# Low_jitter_CLK_bypass.net
KiCad netlist of a schematic drawn in Altium Designer
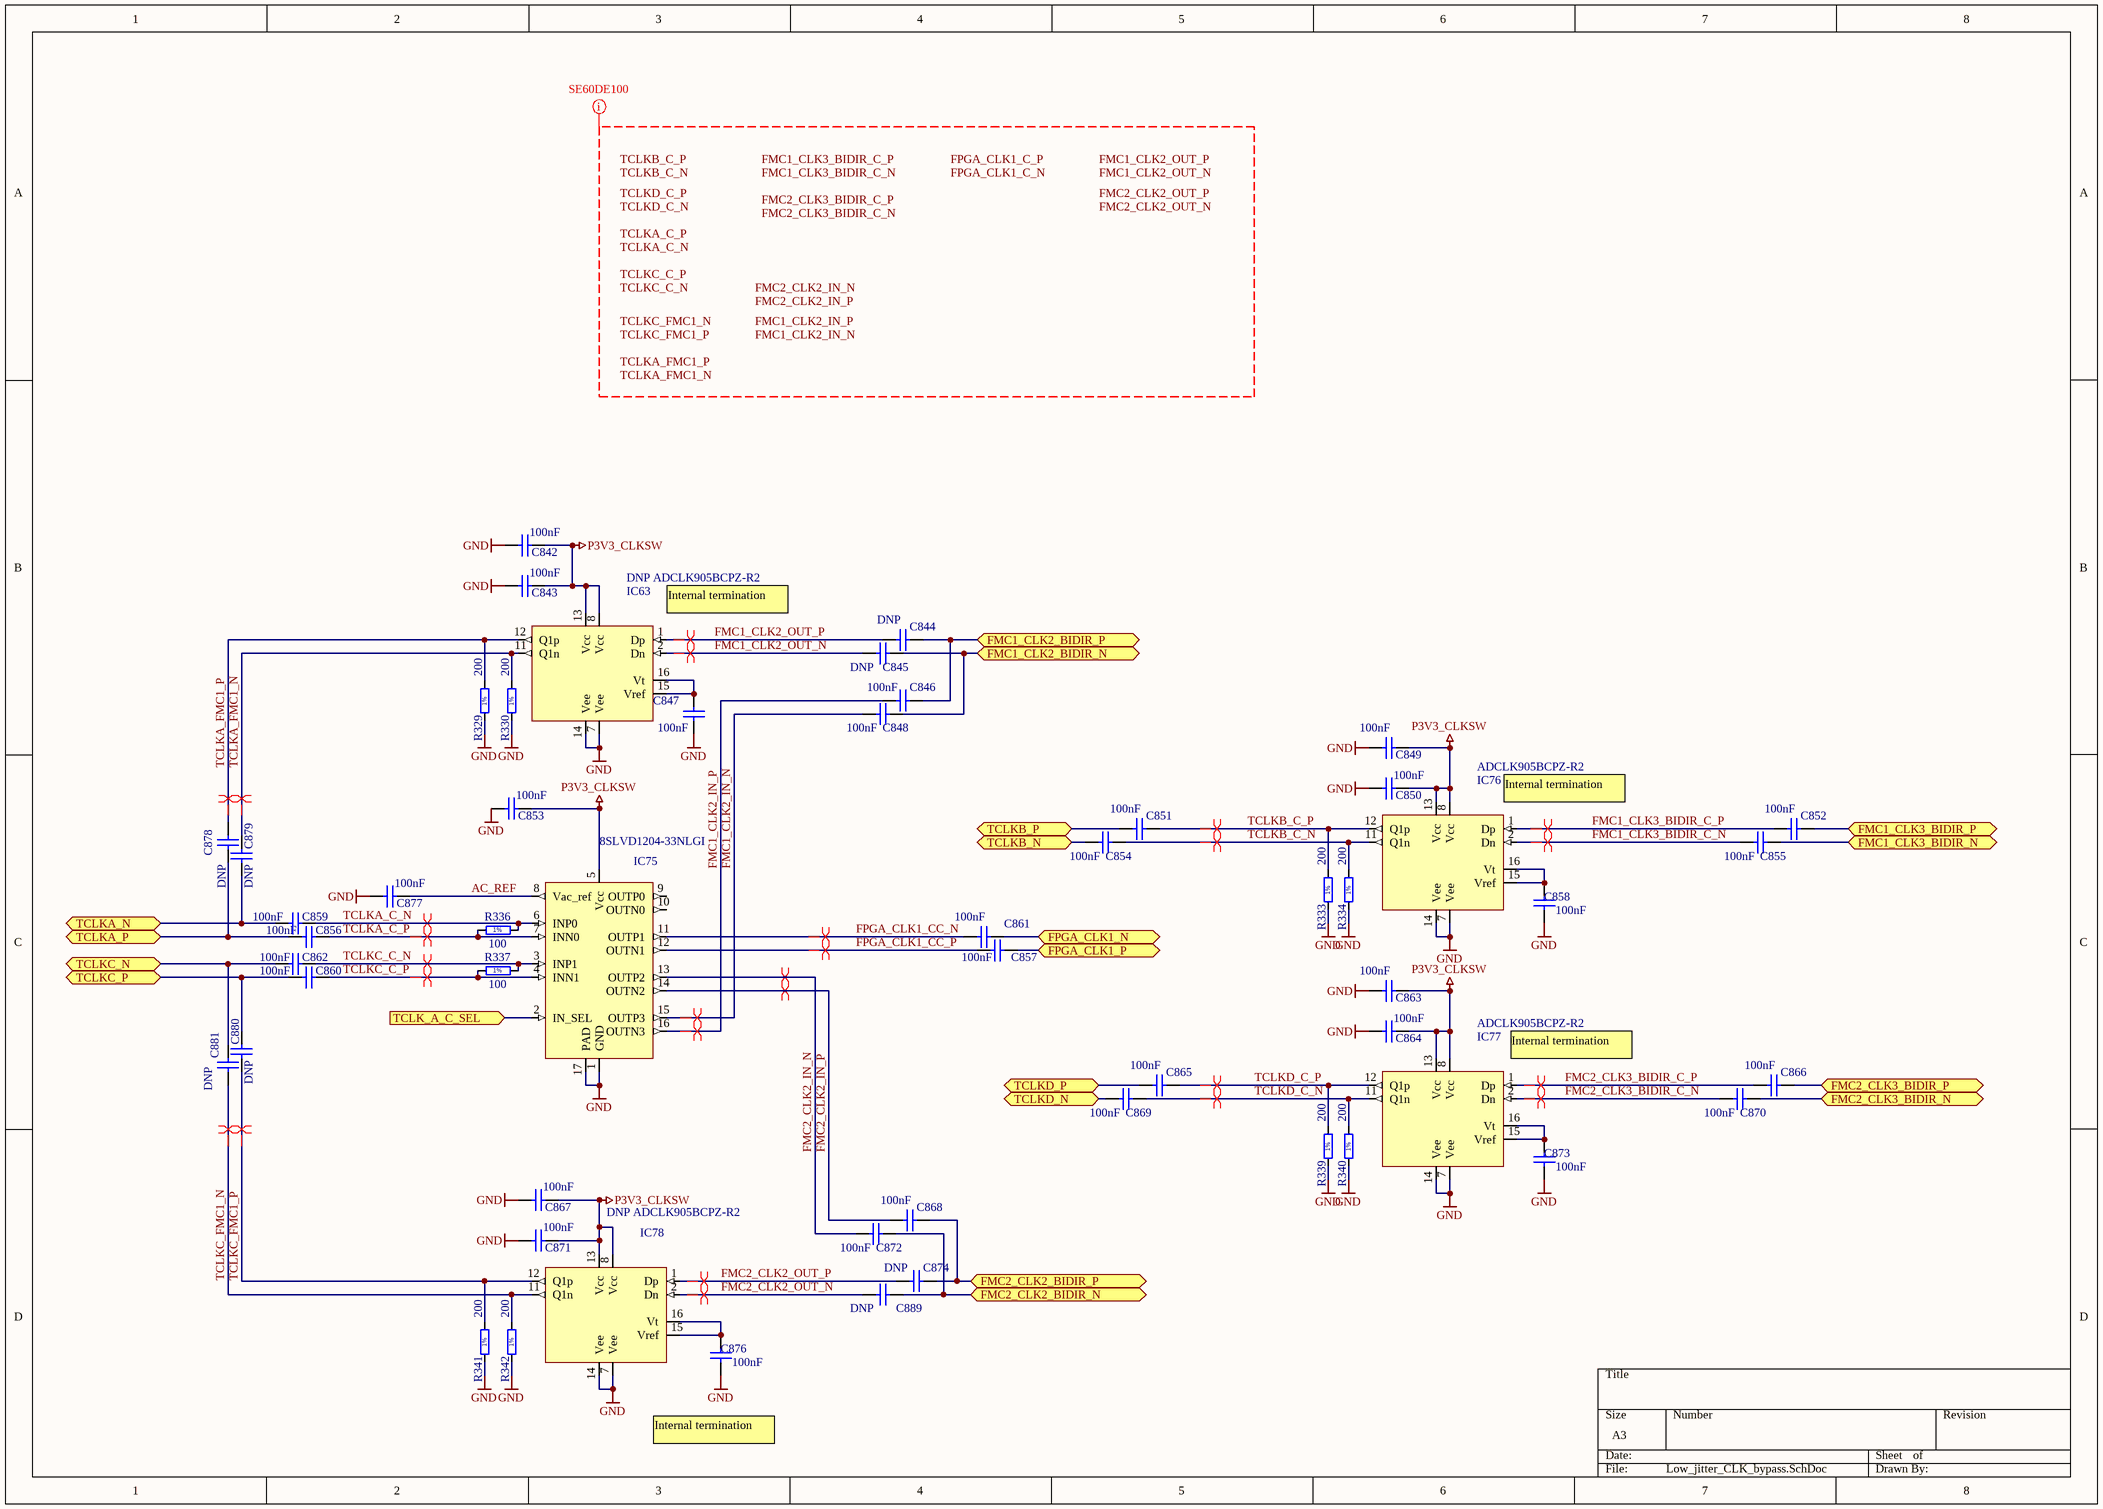
[diagram p0: Low_jitter_CLK_bypass.SchDoc]

(export (version "E")
  (design (tool "Eeschema 10.0.6"))
  (components
    (comp (ref "C842")
      (value "100nF")
      (footprint "CAPC0603X33N")
      (description "Non-polarised capacitor")
      (fields
        (field (name "PART NUMBER") "CC0201_100NF_6.3V_10%_X5R")
        (field (name "VOLTAGE") "6.3V")
        (field (name "AUTHOR") "CERN DEM JLC")
      )
      (libsource (lib "Capacitors") (part "Capacitor - non polarized"))
    )
    (comp (ref "C843")
      (value "100nF")
      (footprint "CAPC0603X33N")
      (description "Non-polarised capacitor")
      (fields
        (field (name "PART NUMBER") "CC0201_100NF_6.3V_10%_X5R")
        (field (name "VOLTAGE") "6.3V")
        (field (name "AUTHOR") "CERN DEM JLC")
      )
      (libsource (lib "Capacitors") (part "Capacitor - non polarized"))
    )
    (comp (ref "C844")
      (value "DNP")
      (footprint "CAPC0603X33N")
      (description "Non-polarised capacitor")
      (fields
        (field (name "PART NUMBER") "CC0201_100NF_6.3V_10%_X5R")
        (field (name "VOLTAGE") "6.3V")
        (field (name "AUTHOR") "CERN DEM JLC")
      )
      (libsource (lib "Capacitors") (part "Capacitor - non polarized"))
    )
    (comp (ref "C845")
      (value "DNP")
      (footprint "CAPC0603X33N")
      (description "Non-polarised capacitor")
      (fields
        (field (name "PART NUMBER") "CC0201_100NF_6.3V_10%_X5R")
        (field (name "VOLTAGE") "6.3V")
        (field (name "AUTHOR") "CERN DEM JLC")
      )
      (libsource (lib "Capacitors") (part "Capacitor - non polarized"))
    )
    (comp (ref "C846")
      (value "100nF")
      (footprint "CAPC0603X33N")
      (description "Non-polarised capacitor")
      (fields
        (field (name "PART NUMBER") "CC0201_100NF_6.3V_10%_X5R")
        (field (name "VOLTAGE") "6.3V")
        (field (name "AUTHOR") "CERN DEM JLC")
      )
      (libsource (lib "Capacitors") (part "Capacitor - non polarized"))
    )
    (comp (ref "C847")
      (value "100nF")
      (footprint "CAPC0603X33N")
      (description "Non-polarised capacitor")
      (fields
        (field (name "PART NUMBER") "CC0201_100NF_6.3V_10%_X5R")
        (field (name "VOLTAGE") "6.3V")
        (field (name "AUTHOR") "CERN DEM JLC")
      )
      (libsource (lib "Capacitors") (part "Capacitor - non polarized"))
    )
    (comp (ref "C848")
      (value "100nF")
      (footprint "CAPC0603X33N")
      (description "Non-polarised capacitor")
      (fields
        (field (name "PART NUMBER") "CC0201_100NF_6.3V_10%_X5R")
        (field (name "VOLTAGE") "6.3V")
        (field (name "AUTHOR") "CERN DEM JLC")
      )
      (libsource (lib "Capacitors") (part "Capacitor - non polarized"))
    )
    (comp (ref "C849")
      (value "100nF")
      (footprint "CAPC0603X33N")
      (description "Non-polarised capacitor")
      (fields
        (field (name "PART NUMBER") "CC0201_100NF_6.3V_10%_X5R")
        (field (name "VOLTAGE") "6.3V")
        (field (name "AUTHOR") "CERN DEM JLC")
      )
      (libsource (lib "Capacitors") (part "Capacitor - non polarized"))
    )
    (comp (ref "C850")
      (value "100nF")
      (footprint "CAPC0603X33N")
      (description "Non-polarised capacitor")
      (fields
        (field (name "PART NUMBER") "CC0201_100NF_6.3V_10%_X5R")
        (field (name "VOLTAGE") "6.3V")
        (field (name "AUTHOR") "CERN DEM JLC")
      )
      (libsource (lib "Capacitors") (part "Capacitor - non polarized"))
    )
    (comp (ref "C851")
      (value "100nF")
      (footprint "CAPC0603X33N")
      (description "Non-polarised capacitor")
      (fields
        (field (name "PART NUMBER") "CC0201_100NF_6.3V_10%_X5R")
        (field (name "VOLTAGE") "6.3V")
        (field (name "AUTHOR") "CERN DEM JLC")
      )
      (libsource (lib "Capacitors") (part "Capacitor - non polarized"))
    )
    (comp (ref "C852")
      (value "100nF")
      (footprint "CAPC0603X33N")
      (description "Non-polarised capacitor")
      (fields
        (field (name "PART NUMBER") "CC0201_100NF_6.3V_10%_X5R")
        (field (name "VOLTAGE") "6.3V")
        (field (name "AUTHOR") "CERN DEM JLC")
      )
      (libsource (lib "Capacitors") (part "Capacitor - non polarized"))
    )
    (comp (ref "C853")
      (value "100nF")
      (footprint "CAPC0603X33N")
      (description "Non-polarised capacitor")
      (fields
        (field (name "PART NUMBER") "CC0201_100NF_6.3V_10%_X5R")
        (field (name "VOLTAGE") "6.3V")
        (field (name "AUTHOR") "CERN DEM JLC")
      )
      (libsource (lib "Capacitors") (part "Capacitor - non polarized"))
    )
    (comp (ref "C854")
      (value "100nF")
      (footprint "CAPC0603X33N")
      (description "Non-polarised capacitor")
      (fields
        (field (name "PART NUMBER") "CC0201_100NF_6.3V_10%_X5R")
        (field (name "VOLTAGE") "6.3V")
        (field (name "AUTHOR") "CERN DEM JLC")
      )
      (libsource (lib "Capacitors") (part "Capacitor - non polarized"))
    )
    (comp (ref "C855")
      (value "100nF")
      (footprint "CAPC0603X33N")
      (description "Non-polarised capacitor")
      (fields
        (field (name "PART NUMBER") "CC0201_100NF_6.3V_10%_X5R")
        (field (name "VOLTAGE") "6.3V")
        (field (name "AUTHOR") "CERN DEM JLC")
      )
      (libsource (lib "Capacitors") (part "Capacitor - non polarized"))
    )
    (comp (ref "C856")
      (value "100nF")
      (footprint "CAPC0603X33N")
      (description "Non-polarised capacitor")
      (fields
        (field (name "PART NUMBER") "CC0201_100NF_6.3V_10%_X5R")
        (field (name "VOLTAGE") "6.3V")
        (field (name "AUTHOR") "CERN DEM JLC")
      )
      (libsource (lib "Capacitors") (part "Capacitor - non polarized"))
    )
    (comp (ref "C857")
      (value "100nF")
      (footprint "CAPC0603X33N")
      (description "Non-polarised capacitor")
      (fields
        (field (name "PART NUMBER") "CC0201_100NF_6.3V_10%_X5R")
        (field (name "VOLTAGE") "6.3V")
        (field (name "AUTHOR") "CERN DEM JLC")
      )
      (libsource (lib "Capacitors") (part "Capacitor - non polarized"))
    )
    (comp (ref "C858")
      (value "100nF")
      (footprint "CAPC0603X33N")
      (description "Non-polarised capacitor")
      (fields
        (field (name "PART NUMBER") "CC0201_100NF_6.3V_10%_X5R")
        (field (name "VOLTAGE") "6.3V")
        (field (name "AUTHOR") "CERN DEM JLC")
      )
      (libsource (lib "Capacitors") (part "Capacitor - non polarized"))
    )
    (comp (ref "C859")
      (value "100nF")
      (footprint "CAPC0603X33N")
      (description "Non-polarised capacitor")
      (fields
        (field (name "PART NUMBER") "CC0201_100NF_6.3V_10%_X5R")
        (field (name "VOLTAGE") "6.3V")
        (field (name "AUTHOR") "CERN DEM JLC")
      )
      (libsource (lib "Capacitors") (part "Capacitor - non polarized"))
    )
    (comp (ref "C860")
      (value "100nF")
      (footprint "CAPC0603X33N")
      (description "Non-polarised capacitor")
      (fields
        (field (name "PART NUMBER") "CC0201_100NF_6.3V_10%_X5R")
        (field (name "VOLTAGE") "6.3V")
        (field (name "AUTHOR") "CERN DEM JLC")
      )
      (libsource (lib "Capacitors") (part "Capacitor - non polarized"))
    )
    (comp (ref "C861")
      (value "100nF")
      (footprint "CAPC0603X33N")
      (description "Non-polarised capacitor")
      (fields
        (field (name "PART NUMBER") "CC0201_100NF_6.3V_10%_X5R")
        (field (name "VOLTAGE") "6.3V")
        (field (name "AUTHOR") "CERN DEM JLC")
      )
      (libsource (lib "Capacitors") (part "Capacitor - non polarized"))
    )
    (comp (ref "C862")
      (value "100nF")
      (footprint "CAPC0603X33N")
      (description "Non-polarised capacitor")
      (fields
        (field (name "PART NUMBER") "CC0201_100NF_6.3V_10%_X5R")
        (field (name "VOLTAGE") "6.3V")
        (field (name "AUTHOR") "CERN DEM JLC")
      )
      (libsource (lib "Capacitors") (part "Capacitor - non polarized"))
    )
    (comp (ref "C863")
      (value "100nF")
      (footprint "CAPC0603X33N")
      (description "Non-polarised capacitor")
      (fields
        (field (name "PART NUMBER") "CC0201_100NF_6.3V_10%_X5R")
        (field (name "VOLTAGE") "6.3V")
        (field (name "AUTHOR") "CERN DEM JLC")
      )
      (libsource (lib "Capacitors") (part "Capacitor - non polarized"))
    )
    (comp (ref "C864")
      (value "100nF")
      (footprint "CAPC0603X33N")
      (description "Non-polarised capacitor")
      (fields
        (field (name "PART NUMBER") "CC0201_100NF_6.3V_10%_X5R")
        (field (name "VOLTAGE") "6.3V")
        (field (name "AUTHOR") "CERN DEM JLC")
      )
      (libsource (lib "Capacitors") (part "Capacitor - non polarized"))
    )
    (comp (ref "C865")
      (value "100nF")
      (footprint "CAPC0603X33N")
      (description "Non-polarised capacitor")
      (fields
        (field (name "PART NUMBER") "CC0201_100NF_6.3V_10%_X5R")
        (field (name "VOLTAGE") "6.3V")
        (field (name "AUTHOR") "CERN DEM JLC")
      )
      (libsource (lib "Capacitors") (part "Capacitor - non polarized"))
    )
    (comp (ref "C866")
      (value "100nF")
      (footprint "CAPC0603X33N")
      (description "Non-polarised capacitor")
      (fields
        (field (name "PART NUMBER") "CC0201_100NF_6.3V_10%_X5R")
        (field (name "VOLTAGE") "6.3V")
        (field (name "AUTHOR") "CERN DEM JLC")
      )
      (libsource (lib "Capacitors") (part "Capacitor - non polarized"))
    )
    (comp (ref "C867")
      (value "100nF")
      (footprint "CAPC0603X33N")
      (description "Non-polarised capacitor")
      (fields
        (field (name "PART NUMBER") "CC0201_100NF_6.3V_10%_X5R")
        (field (name "VOLTAGE") "6.3V")
        (field (name "AUTHOR") "CERN DEM JLC")
      )
      (libsource (lib "Capacitors") (part "Capacitor - non polarized"))
    )
    (comp (ref "C868")
      (value "100nF")
      (footprint "CAPC0603X33N")
      (description "Non-polarised capacitor")
      (fields
        (field (name "PART NUMBER") "CC0201_100NF_6.3V_10%_X5R")
        (field (name "VOLTAGE") "6.3V")
        (field (name "AUTHOR") "CERN DEM JLC")
      )
      (libsource (lib "Capacitors") (part "Capacitor - non polarized"))
    )
    (comp (ref "C869")
      (value "100nF")
      (footprint "CAPC0603X33N")
      (description "Non-polarised capacitor")
      (fields
        (field (name "PART NUMBER") "CC0201_100NF_6.3V_10%_X5R")
        (field (name "VOLTAGE") "6.3V")
        (field (name "AUTHOR") "CERN DEM JLC")
      )
      (libsource (lib "Capacitors") (part "Capacitor - non polarized"))
    )
    (comp (ref "C870")
      (value "100nF")
      (footprint "CAPC0603X33N")
      (description "Non-polarised capacitor")
      (fields
        (field (name "PART NUMBER") "CC0201_100NF_6.3V_10%_X5R")
        (field (name "VOLTAGE") "6.3V")
        (field (name "AUTHOR") "CERN DEM JLC")
      )
      (libsource (lib "Capacitors") (part "Capacitor - non polarized"))
    )
    (comp (ref "C871")
      (value "100nF")
      (footprint "CAPC0603X33N")
      (description "Non-polarised capacitor")
      (fields
        (field (name "PART NUMBER") "CC0201_100NF_6.3V_10%_X5R")
        (field (name "VOLTAGE") "6.3V")
        (field (name "AUTHOR") "CERN DEM JLC")
      )
      (libsource (lib "Capacitors") (part "Capacitor - non polarized"))
    )
    (comp (ref "C872")
      (value "100nF")
      (footprint "CAPC0603X33N")
      (description "Non-polarised capacitor")
      (fields
        (field (name "PART NUMBER") "CC0201_100NF_6.3V_10%_X5R")
        (field (name "VOLTAGE") "6.3V")
        (field (name "AUTHOR") "CERN DEM JLC")
      )
      (libsource (lib "Capacitors") (part "Capacitor - non polarized"))
    )
    (comp (ref "C873")
      (value "100nF")
      (footprint "CAPC0603X33N")
      (description "Non-polarised capacitor")
      (fields
        (field (name "PART NUMBER") "CC0201_100NF_6.3V_10%_X5R")
        (field (name "VOLTAGE") "6.3V")
        (field (name "AUTHOR") "CERN DEM JLC")
      )
      (libsource (lib "Capacitors") (part "Capacitor - non polarized"))
    )
    (comp (ref "C874")
      (value "DNP")
      (footprint "CAPC0603X33N")
      (description "Non-polarised capacitor")
      (fields
        (field (name "PART NUMBER") "CC0201_100NF_6.3V_10%_X5R")
        (field (name "VOLTAGE") "6.3V")
        (field (name "AUTHOR") "CERN DEM JLC")
      )
      (libsource (lib "Capacitors") (part "Capacitor - non polarized"))
    )
    (comp (ref "C876")
      (value "100nF")
      (footprint "CAPC0603X33N")
      (description "Non-polarised capacitor")
      (fields
        (field (name "PART NUMBER") "CC0201_100NF_6.3V_10%_X5R")
        (field (name "VOLTAGE") "6.3V")
        (field (name "AUTHOR") "CERN DEM JLC")
      )
      (libsource (lib "Capacitors") (part "Capacitor - non polarized"))
    )
    (comp (ref "C877")
      (value "100nF")
      (footprint "CAPC0603X33N")
      (description "Non-polarised capacitor")
      (fields
        (field (name "PART NUMBER") "CC0201_100NF_6.3V_10%_X5R")
        (field (name "VOLTAGE") "6.3V")
        (field (name "AUTHOR") "CERN DEM JLC")
      )
      (libsource (lib "Capacitors") (part "Capacitor - non polarized"))
    )
    (comp (ref "C878")
      (value "DNP")
      (footprint "CAPC0603X33N")
      (description "Non-polarised capacitor")
      (fields
        (field (name "PART NUMBER") "CC0201_100NF_6.3V_10%_X5R")
        (field (name "VOLTAGE") "6.3V")
        (field (name "AUTHOR") "CERN DEM JLC")
      )
      (libsource (lib "Capacitors") (part "Capacitor - non polarized"))
    )
    (comp (ref "C879")
      (value "DNP")
      (footprint "CAPC0603X33N")
      (description "Non-polarised capacitor")
      (fields
        (field (name "PART NUMBER") "CC0201_100NF_6.3V_10%_X5R")
        (field (name "VOLTAGE") "6.3V")
        (field (name "AUTHOR") "CERN DEM JLC")
      )
      (libsource (lib "Capacitors") (part "Capacitor - non polarized"))
    )
    (comp (ref "C880")
      (value "DNP")
      (footprint "CAPC0603X33N")
      (description "Non-polarised capacitor")
      (fields
        (field (name "PART NUMBER") "CC0201_100NF_6.3V_10%_X5R")
        (field (name "VOLTAGE") "6.3V")
        (field (name "AUTHOR") "CERN DEM JLC")
      )
      (libsource (lib "Capacitors") (part "Capacitor - non polarized"))
    )
    (comp (ref "C881")
      (value "DNP")
      (footprint "CAPC0603X33N")
      (description "Non-polarised capacitor")
      (fields
        (field (name "PART NUMBER") "CC0201_100NF_6.3V_10%_X5R")
        (field (name "VOLTAGE") "6.3V")
        (field (name "AUTHOR") "CERN DEM JLC")
      )
      (libsource (lib "Capacitors") (part "Capacitor - non polarized"))
    )
    (comp (ref "C889")
      (value "DNP")
      (footprint "CAPC0603X33N")
      (description "Non-polarised capacitor")
      (fields
        (field (name "PART NUMBER") "CC0201_100NF_6.3V_10%_X5R")
        (field (name "VOLTAGE") "6.3V")
        (field (name "AUTHOR") "CERN DEM JLC")
      )
      (libsource (lib "Capacitors") (part "Capacitor - non polarized"))
    )
    (comp (ref "IC63")
      (value "DNP ADCLK905BCPZ-R2")
      (footprint "CP-16-3")
      (description "clock distributor")
      (libsource (lib "LIBRARY_SCH") (part "CLOCK_ADCLK905"))
    )
    (comp (ref "IC75")
      (value "8SLVD1204-33NLGI")
      (footprint "QFN50P300X300X100-16N")
      (description "2:4, LVDS Output Fanout Buffer, 3.3V")
      (libsource (lib "LIBRARY_SCH") (part "CLOCK_IDT8SLVD1204-33"))
    )
    (comp (ref "IC76")
      (value "ADCLK905BCPZ-R2")
      (footprint "CP-16-3")
      (description "clock distributor")
      (libsource (lib "LIBRARY_SCH") (part "CLOCK_ADCLK905"))
    )
    (comp (ref "IC77")
      (value "ADCLK905BCPZ-R2")
      (footprint "CP-16-3")
      (description "clock distributor")
      (libsource (lib "LIBRARY_SCH") (part "CLOCK_ADCLK905"))
    )
    (comp (ref "IC78")
      (value "DNP ADCLK905BCPZ-R2")
      (footprint "CP-16-3")
      (description "clock distributor")
      (libsource (lib "LIBRARY_SCH") (part "CLOCK_ADCLK905"))
    )
    (comp (ref "R329")
      (value "200")
      (footprint "RESC1005X40N")
      (description "Resistor - 1%")
      (fields
        (field (name "PART NUMBER") "R0402_200R_1%_0.0625W_100PPM")
        (field (name "POWER") "0.0625W")
        (field (name "AUTHOR") "CERN DEM JLC")
      )
      (libsource (lib "Resistors") (part "Resistor - 1%"))
    )
    (comp (ref "R330")
      (value "200")
      (footprint "RESC1005X40N")
      (description "Resistor - 1%")
      (fields
        (field (name "PART NUMBER") "R0402_200R_1%_0.0625W_100PPM")
        (field (name "POWER") "0.0625W")
        (field (name "AUTHOR") "CERN DEM JLC")
      )
      (libsource (lib "Resistors") (part "Resistor - 1%"))
    )
    (comp (ref "R333")
      (value "200")
      (footprint "RESC1005X40N")
      (description "Resistor - 1%")
      (fields
        (field (name "PART NUMBER") "R0402_200R_1%_0.0625W_100PPM")
        (field (name "POWER") "0.0625W")
        (field (name "AUTHOR") "CERN DEM JLC")
      )
      (libsource (lib "Resistors") (part "Resistor - 1%"))
    )
    (comp (ref "R334")
      (value "200")
      (footprint "RESC1005X40N")
      (description "Resistor - 1%")
      (fields
        (field (name "PART NUMBER") "R0402_200R_1%_0.0625W_100PPM")
        (field (name "POWER") "0.0625W")
        (field (name "AUTHOR") "CERN DEM JLC")
      )
      (libsource (lib "Resistors") (part "Resistor - 1%"))
    )
    (comp (ref "R336")
      (value "100")
      (footprint "RESC1005X40N")
      (description "Resistor - 1%")
      (fields
        (field (name "PART NUMBER") "R0402_100R_1%_0.0625W_100PPM")
        (field (name "POWER") "0.0625W")
        (field (name "AUTHOR") "CERN DEM JLC")
      )
      (libsource (lib "Resistors") (part "Resistor - 1%"))
    )
    (comp (ref "R337")
      (value "100")
      (footprint "RESC1005X40N")
      (description "Resistor - 1%")
      (fields
        (field (name "PART NUMBER") "R0402_100R_1%_0.0625W_100PPM")
        (field (name "POWER") "0.0625W")
        (field (name "AUTHOR") "CERN DEM JLC")
      )
      (libsource (lib "Resistors") (part "Resistor - 1%"))
    )
    (comp (ref "R339")
      (value "200")
      (footprint "RESC1005X40N")
      (description "Resistor - 1%")
      (fields
        (field (name "PART NUMBER") "R0402_200R_1%_0.0625W_100PPM")
        (field (name "POWER") "0.0625W")
        (field (name "AUTHOR") "CERN DEM JLC")
      )
      (libsource (lib "Resistors") (part "Resistor - 1%"))
    )
    (comp (ref "R340")
      (value "200")
      (footprint "RESC1005X40N")
      (description "Resistor - 1%")
      (fields
        (field (name "PART NUMBER") "R0402_200R_1%_0.0625W_100PPM")
        (field (name "POWER") "0.0625W")
        (field (name "AUTHOR") "CERN DEM JLC")
      )
      (libsource (lib "Resistors") (part "Resistor - 1%"))
    )
    (comp (ref "R341")
      (value "200")
      (footprint "RESC1005X40N")
      (description "Resistor - 1%")
      (fields
        (field (name "PART NUMBER") "R0402_200R_1%_0.0625W_100PPM")
        (field (name "POWER") "0.0625W")
        (field (name "AUTHOR") "CERN DEM JLC")
      )
      (libsource (lib "Resistors") (part "Resistor - 1%"))
    )
    (comp (ref "R342")
      (value "200")
      (footprint "RESC1005X40N")
      (description "Resistor - 1%")
      (fields
        (field (name "PART NUMBER") "R0402_200R_1%_0.0625W_100PPM")
        (field (name "POWER") "0.0625W")
        (field (name "AUTHOR") "CERN DEM JLC")
      )
      (libsource (lib "Resistors") (part "Resistor - 1%"))
    )
  )
  (nets
    (net (code "1") (name "/AC_REF") (class "Default")
      (node (ref "C877") (pin "2") (pinfunction "2_2") (pintype "passive"))
      (node (ref "IC75") (pin "8") (pinfunction "Vac_ref_8") (pintype "output"))
    )
    (net (code "2") (name "/FMC1_CLK2_BIDIR_N") (class "Default")
      (node (ref "C845") (pin "2") (pinfunction "2_2") (pintype "passive"))
      (node (ref "C848") (pin "2") (pinfunction "2_2") (pintype "passive"))
    )
    (net (code "3") (name "/FMC1_CLK2_BIDIR_P") (class "Default")
      (node (ref "C844") (pin "2") (pinfunction "2_2") (pintype "passive"))
      (node (ref "C846") (pin "2") (pinfunction "2_2") (pintype "passive"))
    )
    (net (code "4") (name "/FMC1_CLK2_IN_N") (class "Default")
      (node (ref "C848") (pin "1") (pinfunction "1_1") (pintype "passive"))
      (node (ref "IC75") (pin "15") (pinfunction "OUTP3_15") (pintype "output"))
    )
    (net (code "5") (name "/FMC1_CLK2_IN_P") (class "Default")
      (node (ref "C846") (pin "1") (pinfunction "1_1") (pintype "passive"))
      (node (ref "IC75") (pin "16") (pinfunction "OUTN3_16") (pintype "output"))
    )
    (net (code "6") (name "/FMC1_CLK2_OUT_N") (class "Default")
      (node (ref "C845") (pin "1") (pinfunction "1_1") (pintype "passive"))
      (node (ref "IC63") (pin "2") (pinfunction "Dn_2") (pintype "input"))
    )
    (net (code "7") (name "/FMC1_CLK2_OUT_P") (class "Default")
      (node (ref "C844") (pin "1") (pinfunction "1_1") (pintype "passive"))
      (node (ref "IC63") (pin "1") (pinfunction "Dp_1") (pintype "input"))
    )
    (net (code "8") (name "/FMC1_CLK3_BIDIR_C_N") (class "Default")
      (node (ref "C855") (pin "1") (pinfunction "1_1") (pintype "passive"))
      (node (ref "IC76") (pin "2") (pinfunction "Dn_2") (pintype "input"))
    )
    (net (code "9") (name "/FMC1_CLK3_BIDIR_C_P") (class "Default")
      (node (ref "C852") (pin "1") (pinfunction "1_1") (pintype "passive"))
      (node (ref "IC76") (pin "1") (pinfunction "Dp_1") (pintype "input"))
    )
    (net (code "10") (name "/FMC1_CLK3_BIDIR_N") (class "Default")
      (node (ref "C855") (pin "2") (pinfunction "2_2") (pintype "passive"))
    )
    (net (code "11") (name "/FMC1_CLK3_BIDIR_P") (class "Default")
      (node (ref "C852") (pin "2") (pinfunction "2_2") (pintype "passive"))
    )
    (net (code "12") (name "/FMC2_CLK2_BIDIR_N") (class "Default")
      (node (ref "C872") (pin "2") (pinfunction "2_2") (pintype "passive"))
      (node (ref "C889") (pin "2") (pinfunction "2_2") (pintype "passive"))
    )
    (net (code "13") (name "/FMC2_CLK2_BIDIR_P") (class "Default")
      (node (ref "C868") (pin "2") (pinfunction "2_2") (pintype "passive"))
      (node (ref "C874") (pin "2") (pinfunction "2_2") (pintype "passive"))
    )
    (net (code "14") (name "/FMC2_CLK2_IN_N") (class "Default")
      (node (ref "C872") (pin "1") (pinfunction "1_1") (pintype "passive"))
      (node (ref "IC75") (pin "13") (pinfunction "OUTP2_13") (pintype "output"))
    )
    (net (code "15") (name "/FMC2_CLK2_IN_P") (class "Default")
      (node (ref "C868") (pin "1") (pinfunction "1_1") (pintype "passive"))
      (node (ref "IC75") (pin "14") (pinfunction "OUTN2_14") (pintype "output"))
    )
    (net (code "16") (name "/FMC2_CLK2_OUT_N") (class "Default")
      (node (ref "C889") (pin "1") (pinfunction "1_1") (pintype "passive"))
      (node (ref "IC78") (pin "2") (pinfunction "Dn_2") (pintype "input"))
    )
    (net (code "17") (name "/FMC2_CLK2_OUT_P") (class "Default")
      (node (ref "C874") (pin "1") (pinfunction "1_1") (pintype "passive"))
      (node (ref "IC78") (pin "1") (pinfunction "Dp_1") (pintype "input"))
    )
    (net (code "18") (name "/FMC2_CLK3_BIDIR_C_N") (class "Default")
      (node (ref "C870") (pin "1") (pinfunction "1_1") (pintype "passive"))
      (node (ref "IC77") (pin "2") (pinfunction "Dn_2") (pintype "input"))
    )
    (net (code "19") (name "/FMC2_CLK3_BIDIR_C_P") (class "Default")
      (node (ref "C866") (pin "1") (pinfunction "1_1") (pintype "passive"))
      (node (ref "IC77") (pin "1") (pinfunction "Dp_1") (pintype "input"))
    )
    (net (code "20") (name "/FMC2_CLK3_BIDIR_N") (class "Default")
      (node (ref "C870") (pin "2") (pinfunction "2_2") (pintype "passive"))
    )
    (net (code "21") (name "/FMC2_CLK3_BIDIR_P") (class "Default")
      (node (ref "C866") (pin "2") (pinfunction "2_2") (pintype "passive"))
    )
    (net (code "22") (name "/FPGA_CLK1_CC_N") (class "Default")
      (node (ref "C861") (pin "1") (pinfunction "1_1") (pintype "passive"))
      (node (ref "IC75") (pin "11") (pinfunction "OUTP1_11") (pintype "output"))
    )
    (net (code "23") (name "/FPGA_CLK1_CC_P") (class "Default")
      (node (ref "C857") (pin "1") (pinfunction "1_1") (pintype "passive"))
      (node (ref "IC75") (pin "12") (pinfunction "OUTN1_12") (pintype "output"))
    )
    (net (code "26") (name "/FPGA_CLK1_N") (class "Default")
      (node (ref "C861") (pin "2") (pinfunction "2_2") (pintype "passive"))
    )
    (net (code "27") (name "/FPGA_CLK1_P") (class "Default")
      (node (ref "C857") (pin "2") (pinfunction "2_2") (pintype "passive"))
    )
    (net (code "28") (name "/TCLKA_C_N") (class "Default")
      (node (ref "C859") (pin "2") (pinfunction "2_2") (pintype "passive"))
      (node (ref "IC75") (pin "6") (pinfunction "INP0_6") (pintype "input"))
      (node (ref "R336") (pin "2") (pinfunction "2_2") (pintype "passive"))
    )
    (net (code "29") (name "/TCLKA_C_P") (class "Default")
      (node (ref "C856") (pin "2") (pinfunction "2_2") (pintype "passive"))
      (node (ref "IC75") (pin "7") (pinfunction "INN0_7") (pintype "input"))
      (node (ref "R336") (pin "1") (pinfunction "1_1") (pintype "passive"))
    )
    (net (code "30") (name "/TCLKA_FMC1_N") (class "Default")
      (node (ref "C879") (pin "2") (pinfunction "2_2") (pintype "passive"))
      (node (ref "IC63") (pin "11") (pinfunction "Q1n_11") (pintype "output"))
      (node (ref "R330") (pin "2") (pinfunction "2_2") (pintype "passive"))
    )
    (net (code "31") (name "/TCLKA_FMC1_P") (class "Default")
      (node (ref "C878") (pin "2") (pinfunction "2_2") (pintype "passive"))
      (node (ref "IC63") (pin "12") (pinfunction "Q1p_12") (pintype "output"))
      (node (ref "R329") (pin "2") (pinfunction "2_2") (pintype "passive"))
    )
    (net (code "32") (name "/TCLKA_N") (class "Default")
      (node (ref "C859") (pin "1") (pinfunction "1_1") (pintype "passive"))
      (node (ref "C879") (pin "1") (pinfunction "1_1") (pintype "passive"))
    )
    (net (code "33") (name "/TCLKA_P") (class "Default")
      (node (ref "C856") (pin "1") (pinfunction "1_1") (pintype "passive"))
      (node (ref "C878") (pin "1") (pinfunction "1_1") (pintype "passive"))
    )
    (net (code "34") (name "/TCLKB_C_N") (class "Default")
      (node (ref "C854") (pin "2") (pinfunction "2_2") (pintype "passive"))
      (node (ref "IC76") (pin "11") (pinfunction "Q1n_11") (pintype "output"))
      (node (ref "R334") (pin "2") (pinfunction "2_2") (pintype "passive"))
    )
    (net (code "35") (name "/TCLKB_C_P") (class "Default")
      (node (ref "C851") (pin "2") (pinfunction "2_2") (pintype "passive"))
      (node (ref "IC76") (pin "12") (pinfunction "Q1p_12") (pintype "output"))
      (node (ref "R333") (pin "2") (pinfunction "2_2") (pintype "passive"))
    )
    (net (code "36") (name "/TCLKB_N") (class "Default")
      (node (ref "C854") (pin "1") (pinfunction "1_1") (pintype "passive"))
    )
    (net (code "37") (name "/TCLKB_P") (class "Default")
      (node (ref "C851") (pin "1") (pinfunction "1_1") (pintype "passive"))
    )
    (net (code "38") (name "/TCLKC_C_N") (class "Default")
      (node (ref "C862") (pin "2") (pinfunction "2_2") (pintype "passive"))
      (node (ref "IC75") (pin "3") (pinfunction "INP1_3") (pintype "input"))
      (node (ref "R337") (pin "2") (pinfunction "2_2") (pintype "passive"))
    )
    (net (code "39") (name "/TCLKC_C_P") (class "Default")
      (node (ref "C860") (pin "2") (pinfunction "2_2") (pintype "passive"))
      (node (ref "IC75") (pin "4") (pinfunction "INN1_4") (pintype "input"))
      (node (ref "R337") (pin "1") (pinfunction "1_1") (pintype "passive"))
    )
    (net (code "40") (name "/TCLKC_FMC1_N") (class "Default")
      (node (ref "C881") (pin "1") (pinfunction "1_1") (pintype "passive"))
      (node (ref "IC78") (pin "11") (pinfunction "Q1n_11") (pintype "output"))
      (node (ref "R342") (pin "2") (pinfunction "2_2") (pintype "passive"))
    )
    (net (code "41") (name "/TCLKC_FMC1_P") (class "Default")
      (node (ref "C880") (pin "1") (pinfunction "1_1") (pintype "passive"))
      (node (ref "IC78") (pin "12") (pinfunction "Q1p_12") (pintype "output"))
      (node (ref "R341") (pin "2") (pinfunction "2_2") (pintype "passive"))
    )
    (net (code "42") (name "/TCLKC_N") (class "Default")
      (node (ref "C862") (pin "1") (pinfunction "1_1") (pintype "passive"))
      (node (ref "C881") (pin "2") (pinfunction "2_2") (pintype "passive"))
    )
    (net (code "43") (name "/TCLKC_P") (class "Default")
      (node (ref "C860") (pin "1") (pinfunction "1_1") (pintype "passive"))
      (node (ref "C880") (pin "2") (pinfunction "2_2") (pintype "passive"))
    )
    (net (code "44") (name "/TCLKD_C_N") (class "Default")
      (node (ref "C869") (pin "2") (pinfunction "2_2") (pintype "passive"))
      (node (ref "IC77") (pin "11") (pinfunction "Q1n_11") (pintype "output"))
      (node (ref "R340") (pin "2") (pinfunction "2_2") (pintype "passive"))
    )
    (net (code "45") (name "/TCLKD_C_P") (class "Default")
      (node (ref "C865") (pin "2") (pinfunction "2_2") (pintype "passive"))
      (node (ref "IC77") (pin "12") (pinfunction "Q1p_12") (pintype "output"))
      (node (ref "R339") (pin "2") (pinfunction "2_2") (pintype "passive"))
    )
    (net (code "46") (name "/TCLKD_N") (class "Default")
      (node (ref "C869") (pin "1") (pinfunction "1_1") (pintype "passive"))
    )
    (net (code "47") (name "/TCLKD_P") (class "Default")
      (node (ref "C865") (pin "1") (pinfunction "1_1") (pintype "passive"))
    )
    (net (code "48") (name "/TCLK_A_C_SEL") (class "Default")
      (node (ref "IC75") (pin "2") (pinfunction "IN_SEL_2") (pintype "input"))
    )
    (net (code "49") (name "GND") (class "Default")
      (node (ref "C842") (pin "1") (pinfunction "1_1") (pintype "passive"))
      (node (ref "C843") (pin "1") (pinfunction "1_1") (pintype "passive"))
      (node (ref "C847") (pin "1") (pinfunction "1_1") (pintype "passive"))
      (node (ref "C849") (pin "1") (pinfunction "1_1") (pintype "passive"))
      (node (ref "C850") (pin "1") (pinfunction "1_1") (pintype "passive"))
      (node (ref "C853") (pin "1") (pinfunction "1_1") (pintype "passive"))
      (node (ref "C858") (pin "1") (pinfunction "1_1") (pintype "passive"))
      (node (ref "C863") (pin "1") (pinfunction "1_1") (pintype "passive"))
      (node (ref "C864") (pin "1") (pinfunction "1_1") (pintype "passive"))
      (node (ref "C867") (pin "1") (pinfunction "1_1") (pintype "passive"))
      (node (ref "C871") (pin "1") (pinfunction "1_1") (pintype "passive"))
      (node (ref "C873") (pin "1") (pinfunction "1_1") (pintype "passive"))
      (node (ref "C876") (pin "1") (pinfunction "1_1") (pintype "passive"))
      (node (ref "C877") (pin "1") (pinfunction "1_1") (pintype "passive"))
      (node (ref "IC63") (pin "14") (pinfunction "Vee_14") (pintype "power_in"))
      (node (ref "IC63") (pin "7") (pinfunction "Vee_7") (pintype "power_in"))
      (node (ref "IC75") (pin "1") (pinfunction "GND_1") (pintype "power_in"))
      (node (ref "IC75") (pin "17") (pinfunction "PAD_17") (pintype "power_in"))
      (node (ref "IC76") (pin "14") (pinfunction "Vee_14") (pintype "power_in"))
      (node (ref "IC76") (pin "7") (pinfunction "Vee_7") (pintype "power_in"))
      (node (ref "IC77") (pin "14") (pinfunction "Vee_14") (pintype "power_in"))
      (node (ref "IC77") (pin "7") (pinfunction "Vee_7") (pintype "power_in"))
      (node (ref "IC78") (pin "14") (pinfunction "Vee_14") (pintype "power_in"))
      (node (ref "IC78") (pin "7") (pinfunction "Vee_7") (pintype "power_in"))
      (node (ref "R329") (pin "1") (pinfunction "1_1") (pintype "passive"))
      (node (ref "R330") (pin "1") (pinfunction "1_1") (pintype "passive"))
      (node (ref "R333") (pin "1") (pinfunction "1_1") (pintype "passive"))
      (node (ref "R334") (pin "1") (pinfunction "1_1") (pintype "passive"))
      (node (ref "R339") (pin "1") (pinfunction "1_1") (pintype "passive"))
      (node (ref "R340") (pin "1") (pinfunction "1_1") (pintype "passive"))
      (node (ref "R341") (pin "1") (pinfunction "1_1") (pintype "passive"))
      (node (ref "R342") (pin "1") (pinfunction "1_1") (pintype "passive"))
    )
    (net (code "50") (name "Net-(IC63-Vref)") (class "Default")
      (node (ref "C847") (pin "2") (pinfunction "2_2") (pintype "passive"))
      (node (ref "IC63") (pin "15") (pinfunction "Vref_15") (pintype "power_in"))
      (node (ref "IC63") (pin "16") (pinfunction "Vt_16") (pintype "passive"))
    )
    (net (code "51") (name "Net-(IC76-Vref)") (class "Default")
      (node (ref "C858") (pin "2") (pinfunction "2_2") (pintype "passive"))
      (node (ref "IC76") (pin "15") (pinfunction "Vref_15") (pintype "power_in"))
      (node (ref "IC76") (pin "16") (pinfunction "Vt_16") (pintype "passive"))
    )
    (net (code "52") (name "Net-(IC77-Vref)") (class "Default")
      (node (ref "C873") (pin "2") (pinfunction "2_2") (pintype "passive"))
      (node (ref "IC77") (pin "15") (pinfunction "Vref_15") (pintype "power_in"))
      (node (ref "IC77") (pin "16") (pinfunction "Vt_16") (pintype "passive"))
    )
    (net (code "53") (name "Net-(IC78-Vref)") (class "Default")
      (node (ref "C876") (pin "2") (pinfunction "2_2") (pintype "passive"))
      (node (ref "IC78") (pin "15") (pinfunction "Vref_15") (pintype "power_in"))
      (node (ref "IC78") (pin "16") (pinfunction "Vt_16") (pintype "passive"))
    )
    (net (code "54") (name "P3V3_CLKSW") (class "Default")
      (node (ref "C842") (pin "2") (pinfunction "2_2") (pintype "passive"))
      (node (ref "C843") (pin "2") (pinfunction "2_2") (pintype "passive"))
      (node (ref "C849") (pin "2") (pinfunction "2_2") (pintype "passive"))
      (node (ref "C850") (pin "2") (pinfunction "2_2") (pintype "passive"))
      (node (ref "C853") (pin "2") (pinfunction "2_2") (pintype "passive"))
      (node (ref "C863") (pin "2") (pinfunction "2_2") (pintype "passive"))
      (node (ref "C864") (pin "2") (pinfunction "2_2") (pintype "passive"))
      (node (ref "C867") (pin "2") (pinfunction "2_2") (pintype "passive"))
      (node (ref "C871") (pin "2") (pinfunction "2_2") (pintype "passive"))
      (node (ref "IC63") (pin "13") (pinfunction "Vcc_13") (pintype "power_in"))
      (node (ref "IC63") (pin "8") (pinfunction "Vcc_8") (pintype "power_in"))
      (node (ref "IC75") (pin "5") (pinfunction "Vcc_5") (pintype "power_in"))
      (node (ref "IC76") (pin "13") (pinfunction "Vcc_13") (pintype "power_in"))
      (node (ref "IC76") (pin "8") (pinfunction "Vcc_8") (pintype "power_in"))
      (node (ref "IC77") (pin "13") (pinfunction "Vcc_13") (pintype "power_in"))
      (node (ref "IC77") (pin "8") (pinfunction "Vcc_8") (pintype "power_in"))
      (node (ref "IC78") (pin "13") (pinfunction "Vcc_13") (pintype "power_in"))
      (node (ref "IC78") (pin "8") (pinfunction "Vcc_8") (pintype "power_in"))
    )
    (net (code "55") (name "unconnected-(IC75-OUTN0-Pad10)") (class "Default")
      (node (ref "IC75") (pin "10") (pinfunction "OUTN0_10") (pintype "output"))
    )
    (net (code "56") (name "unconnected-(IC75-OUTP0-Pad9)") (class "Default")
      (node (ref "IC75") (pin "9") (pinfunction "OUTP0_9") (pintype "output"))
    )
  )
)
